# Sch_Raspi_Hat.net
KiCad netlist of a schematic drawn in Altium Designer
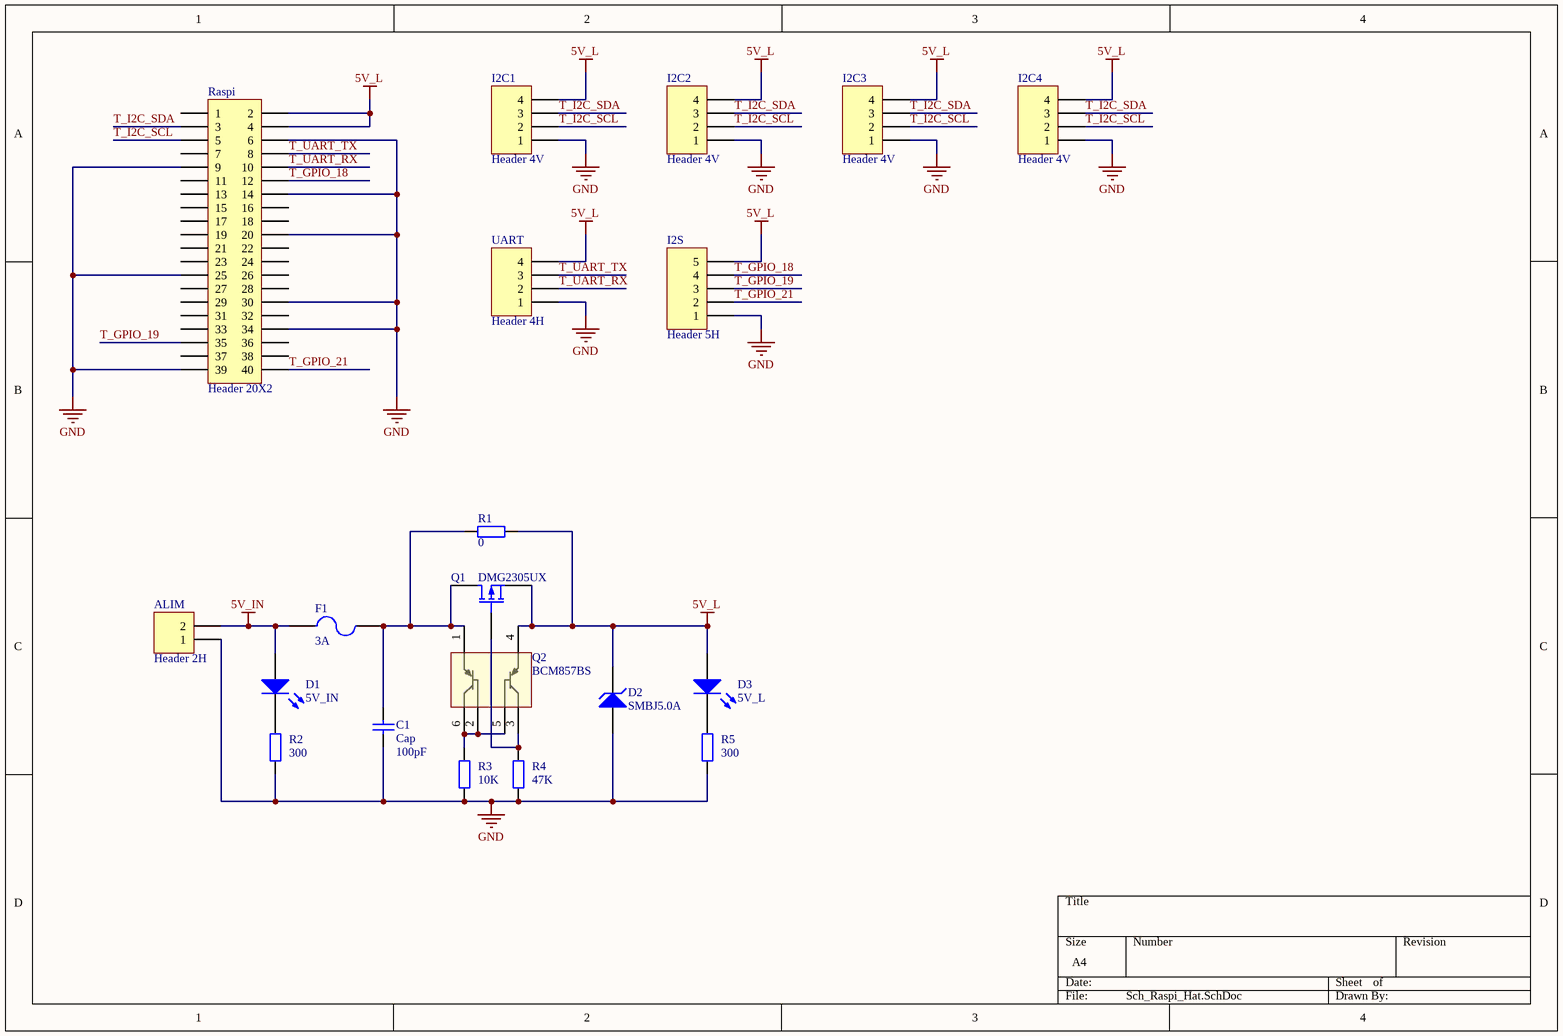
[diagram p0: Sch_Raspi_Hat.SchDoc]

(export (version "E")
  (design (tool "Eeschema 10.0.6"))
  (components
    (comp (ref "ALIM")
      (value "Header 2H")
      (footprint "Molex_MiniFitJr_2x1H")
      (description "Header, 2-Pin, Right Angle")
      (fields (field (name "PUBLISHER") "Altium Limited"))
      (libsource (lib "Miscellaneous Connectors") (part "Header 2H"))
    )
    (comp (ref "C1")
      (value "Cap")
      (footprint "Capacitor 1206")
      (description "Capacitor")
      (fields (field (name "ALTIUM_VALUE") "100pF") (field (name "PUBLISHER") "Altium Limited"))
      (libsource (lib "Miscellaneous Devices") (part "Cap"))
    )
    (comp (ref "D1")
      (value "5V_IN")
      (footprint "KP-3216SEC")
      (description "Typical RED, GREEN, YELLOW, AMBER GaAs LED")
      (fields (field (name "PUBLISHER") "Altium Limited"))
      (libsource (lib "Miscellaneous Devices") (part "LED2"))
    )
    (comp (ref "D2")
      (value "SMBJ5.0A")
      (footprint "SMB")
      (description "Zener Diode")
      (fields (field (name "PUBLISHER") "Altium Limited"))
      (libsource (lib "Miscellaneous Devices") (part "D Zener"))
    )
    (comp (ref "D3")
      (value "5V_L")
      (footprint "KP-3216SEC")
      (description "Typical RED, GREEN, YELLOW, AMBER GaAs LED")
      (fields (field (name "PUBLISHER") "Altium Limited"))
      (libsource (lib "Miscellaneous Devices") (part "LED2"))
    )
    (comp (ref "F1")
      (value "3A")
      (footprint "Resistor 1206")
      (description "Fuse")
      (fields (field (name "PUBLISHER") "Altium Limited"))
      (libsource (lib "Miscellaneous Devices") (part "Fuse 2"))
    )
    (comp (ref "I2C1")
      (value "Header 4V")
      (footprint "B4BXHALFSN")
      (description "Header, 4-Pin, Right Angle")
      (fields (field (name "PUBLISHER") "Altium Limited"))
      (libsource (lib "Miscellaneous Connectors") (part "Header 4H"))
    )
    (comp (ref "I2C2")
      (value "Header 4V")
      (footprint "B4BXHALFSN")
      (description "Header, 4-Pin, Right Angle")
      (fields (field (name "PUBLISHER") "Altium Limited"))
      (libsource (lib "Miscellaneous Connectors") (part "Header 4H"))
    )
    (comp (ref "I2C3")
      (value "Header 4V")
      (footprint "B4BXHALFSN")
      (description "Header, 4-Pin, Right Angle")
      (fields (field (name "PUBLISHER") "Altium Limited"))
      (libsource (lib "Miscellaneous Connectors") (part "Header 4H"))
    )
    (comp (ref "I2C4")
      (value "Header 4V")
      (footprint "B4BXHALFSN")
      (description "Header, 4-Pin, Right Angle")
      (fields (field (name "PUBLISHER") "Altium Limited"))
      (libsource (lib "Miscellaneous Connectors") (part "Header 4H"))
    )
    (comp (ref "I2S")
      (value "Header 5H")
      (footprint "S5B-XH-A")
      (description "Header, 5-Pin, Right Angle")
      (fields (field (name "PUBLISHER") "Altium Limited"))
      (libsource (lib "Miscellaneous Connectors") (part "Header 5H"))
    )
    (comp (ref "Q1")
      (value "DMG2305UX")
      (footprint "SOT23_L")
      (description "P-Channel MOSFET")
      (fields (field (name "PUBLISHER") "Altium Limited"))
      (libsource (lib "Miscellaneous Devices") (part "MOSFET-P"))
    )
    (comp (ref "Q2")
      (value "BCM857BS")
      (footprint "SOT65P210X110-6N")
      (description "Transistor")
      (libsource (lib "SamacSys") (part "BCM857BS"))
    )
    (comp (ref "R1")
      (value "0")
      (footprint "Resistor 1206")
      (description "Resistor")
      (fields (field (name "Comment") "Res2") (field (name "PUBLISHER") "Altium Limited"))
      (libsource (lib "") (part "Res2_1"))
    )
    (comp (ref "R2")
      (value "300")
      (footprint "Resistor 1206")
      (description "Resistor")
      (fields (field (name "Comment") "Res2") (field (name "PUBLISHER") "Altium Limited"))
      (libsource (lib "Miscellaneous Devices") (part "Res2"))
    )
    (comp (ref "R3")
      (value "10K")
      (footprint "Resistor 1206")
      (description "Resistor")
      (fields (field (name "Comment") "Res2") (field (name "PUBLISHER") "Altium Limited"))
      (libsource (lib "Miscellaneous Devices") (part "Res2"))
    )
    (comp (ref "R4")
      (value "47K")
      (footprint "Resistor 1206")
      (description "Resistor")
      (fields (field (name "Comment") "Res2") (field (name "PUBLISHER") "Altium Limited"))
      (libsource (lib "Miscellaneous Devices") (part "Res2"))
    )
    (comp (ref "R5")
      (value "300")
      (footprint "Resistor 1206")
      (description "Resistor")
      (fields (field (name "Comment") "Res2") (field (name "PUBLISHER") "Altium Limited"))
      (libsource (lib "Miscellaneous Devices") (part "Res2"))
    )
    (comp (ref "Raspi")
      (value "Header 20X2")
      (footprint "HDR2X20")
      (description "Header, 20-Pin, Dual row")
      (fields (field (name "PUBLISHER") "Altium Limited"))
      (libsource (lib "Miscellaneous Connectors") (part "Header 20X2"))
    )
    (comp (ref "UART")
      (value "Header 4H")
      (footprint "S4B-XH-A")
      (description "Header, 4-Pin, Right Angle")
      (fields (field (name "PUBLISHER") "Altium Limited"))
      (libsource (lib "Miscellaneous Connectors") (part "Header 4H"))
    )
  )
  (nets
    (net (code "1") (name "/T_GPIO_18") (class "Default")
      (node (ref "I2S") (pin "4") (pinfunction "4_4") (pintype "passive"))
      (node (ref "Raspi") (pin "12") (pinfunction "12_12") (pintype "passive"))
    )
    (net (code "2") (name "/T_GPIO_19") (class "Default")
      (node (ref "I2S") (pin "3") (pinfunction "3_3") (pintype "passive"))
      (node (ref "Raspi") (pin "35") (pinfunction "35_35") (pintype "passive"))
    )
    (net (code "3") (name "/T_GPIO_21") (class "Default")
      (node (ref "I2S") (pin "2") (pinfunction "2_2") (pintype "passive"))
      (node (ref "Raspi") (pin "40") (pinfunction "40_40") (pintype "passive"))
    )
    (net (code "4") (name "/T_I2C_SCL") (class "Default")
      (node (ref "I2C1") (pin "2") (pinfunction "2_2") (pintype "passive"))
      (node (ref "I2C2") (pin "2") (pinfunction "2_2") (pintype "passive"))
      (node (ref "I2C3") (pin "2") (pinfunction "2_2") (pintype "passive"))
      (node (ref "I2C4") (pin "2") (pinfunction "2_2") (pintype "passive"))
      (node (ref "Raspi") (pin "5") (pinfunction "5_5") (pintype "passive"))
    )
    (net (code "5") (name "/T_I2C_SDA") (class "Default")
      (node (ref "I2C1") (pin "3") (pinfunction "3_3") (pintype "passive"))
      (node (ref "I2C2") (pin "3") (pinfunction "3_3") (pintype "passive"))
      (node (ref "I2C3") (pin "3") (pinfunction "3_3") (pintype "passive"))
      (node (ref "I2C4") (pin "3") (pinfunction "3_3") (pintype "passive"))
      (node (ref "Raspi") (pin "3") (pinfunction "3_3") (pintype "passive"))
    )
    (net (code "6") (name "/T_UART_RX") (class "Default")
      (node (ref "Raspi") (pin "10") (pinfunction "10_10") (pintype "passive"))
      (node (ref "UART") (pin "2") (pinfunction "2_2") (pintype "passive"))
    )
    (net (code "7") (name "/T_UART_TX") (class "Default")
      (node (ref "Raspi") (pin "8") (pinfunction "8_8") (pintype "passive"))
      (node (ref "UART") (pin "3") (pinfunction "3_3") (pintype "passive"))
    )
    (net (code "8") (name "5V_IN") (class "Default")
      (node (ref "ALIM") (pin "2") (pinfunction "2_2") (pintype "passive"))
      (node (ref "D1") (pin "1") (pinfunction "A_1") (pintype "passive"))
      (node (ref "F1") (pin "1") (pinfunction "1_1") (pintype "passive"))
    )
    (net (code "9") (name "5V_L") (class "Default")
      (node (ref "D2") (pin "2") (pinfunction "K_2") (pintype "passive"))
      (node (ref "D3") (pin "1") (pinfunction "A_1") (pintype "passive"))
      (node (ref "I2C1") (pin "4") (pinfunction "4_4") (pintype "passive"))
      (node (ref "I2C2") (pin "4") (pinfunction "4_4") (pintype "passive"))
      (node (ref "I2C3") (pin "4") (pinfunction "4_4") (pintype "passive"))
      (node (ref "I2C4") (pin "4") (pinfunction "4_4") (pintype "passive"))
      (node (ref "I2S") (pin "5") (pinfunction "5_5") (pintype "passive"))
      (node (ref "Q1") (pin "3") (pinfunction "S_3") (pintype "passive"))
      (node (ref "Q2") (pin "4") (pinfunction "EMITTER_TR2_4") (pintype "passive"))
      (node (ref "R1") (pin "1") (pinfunction "1_1") (pintype "passive"))
      (node (ref "Raspi") (pin "2") (pinfunction "2_2") (pintype "passive"))
      (node (ref "Raspi") (pin "4") (pinfunction "4_4") (pintype "passive"))
      (node (ref "UART") (pin "4") (pinfunction "4_4") (pintype "passive"))
    )
    (net (code "10") (name "GND") (class "Default")
      (node (ref "ALIM") (pin "1") (pinfunction "1_1") (pintype "passive"))
      (node (ref "C1") (pin "1") (pinfunction "1_1") (pintype "passive"))
      (node (ref "D2") (pin "1") (pinfunction "A_1") (pintype "passive"))
      (node (ref "I2C1") (pin "1") (pinfunction "1_1") (pintype "passive"))
      (node (ref "I2C2") (pin "1") (pinfunction "1_1") (pintype "passive"))
      (node (ref "I2C3") (pin "1") (pinfunction "1_1") (pintype "passive"))
      (node (ref "I2C4") (pin "1") (pinfunction "1_1") (pintype "passive"))
      (node (ref "I2S") (pin "1") (pinfunction "1_1") (pintype "passive"))
      (node (ref "R2") (pin "1") (pinfunction "1_1") (pintype "passive"))
      (node (ref "R3") (pin "1") (pinfunction "1_1") (pintype "passive"))
      (node (ref "R4") (pin "1") (pinfunction "1_1") (pintype "passive"))
      (node (ref "R5") (pin "1") (pinfunction "1_1") (pintype "passive"))
      (node (ref "Raspi") (pin "14") (pinfunction "14_14") (pintype "passive"))
      (node (ref "Raspi") (pin "20") (pinfunction "20_20") (pintype "passive"))
      (node (ref "Raspi") (pin "25") (pinfunction "25_25") (pintype "passive"))
      (node (ref "Raspi") (pin "30") (pinfunction "30_30") (pintype "passive"))
      (node (ref "Raspi") (pin "34") (pinfunction "34_34") (pintype "passive"))
      (node (ref "Raspi") (pin "39") (pinfunction "39_39") (pintype "passive"))
      (node (ref "Raspi") (pin "6") (pinfunction "6_6") (pintype "passive"))
      (node (ref "Raspi") (pin "9") (pinfunction "9_9") (pintype "passive"))
      (node (ref "UART") (pin "1") (pinfunction "1_1") (pintype "passive"))
    )
    (net (code "11") (name "Net-(D1-K)") (class "Default")
      (node (ref "D1") (pin "2") (pinfunction "K_2") (pintype "passive"))
      (node (ref "R2") (pin "2") (pinfunction "2_2") (pintype "passive"))
    )
    (net (code "12") (name "Net-(D3-K)") (class "Default")
      (node (ref "D3") (pin "2") (pinfunction "K_2") (pintype "passive"))
      (node (ref "R5") (pin "2") (pinfunction "2_2") (pintype "passive"))
    )
    (net (code "13") (name "Net-(Q1-D)") (class "Default")
      (node (ref "C1") (pin "2") (pinfunction "2_2") (pintype "passive"))
      (node (ref "F1") (pin "2") (pinfunction "2_2") (pintype "passive"))
      (node (ref "Q1") (pin "1") (pinfunction "D_1") (pintype "passive"))
      (node (ref "Q2") (pin "1") (pinfunction "EMITTER_TR1_1") (pintype "passive"))
      (node (ref "R1") (pin "2") (pinfunction "2_2") (pintype "passive"))
    )
    (net (code "14") (name "Net-(Q1-G)") (class "Default")
      (node (ref "Q1") (pin "2") (pinfunction "G_2") (pintype "passive"))
      (node (ref "Q2") (pin "3") (pinfunction "COLLECTOR_TR2_3") (pintype "passive"))
      (node (ref "R4") (pin "2") (pinfunction "2_2") (pintype "passive"))
    )
    (net (code "15") (name "Net-(Q2-BASE_TR1)") (class "Default")
      (node (ref "Q2") (pin "2") (pinfunction "BASE_TR1_2") (pintype "passive"))
      (node (ref "Q2") (pin "5") (pinfunction "BASE_TR2_5") (pintype "passive"))
      (node (ref "Q2") (pin "6") (pinfunction "COLLECTOR_TR1_6") (pintype "passive"))
      (node (ref "R3") (pin "2") (pinfunction "2_2") (pintype "passive"))
    )
    (net (code "16") (name "unconnected-(Raspi-Pad1)") (class "Default")
      (node (ref "Raspi") (pin "1") (pinfunction "1_1") (pintype "passive"))
    )
    (net (code "17") (name "unconnected-(Raspi-Pad7)") (class "Default")
      (node (ref "Raspi") (pin "7") (pinfunction "7_7") (pintype "passive"))
    )
    (net (code "18") (name "unconnected-(Raspi-Pad11)") (class "Default")
      (node (ref "Raspi") (pin "11") (pinfunction "11_11") (pintype "passive"))
    )
    (net (code "19") (name "unconnected-(Raspi-Pad13)") (class "Default")
      (node (ref "Raspi") (pin "13") (pinfunction "13_13") (pintype "passive"))
    )
    (net (code "20") (name "unconnected-(Raspi-Pad15)") (class "Default")
      (node (ref "Raspi") (pin "15") (pinfunction "15_15") (pintype "passive"))
    )
    (net (code "21") (name "unconnected-(Raspi-Pad16)") (class "Default")
      (node (ref "Raspi") (pin "16") (pinfunction "16_16") (pintype "passive"))
    )
    (net (code "22") (name "unconnected-(Raspi-Pad17)") (class "Default")
      (node (ref "Raspi") (pin "17") (pinfunction "17_17") (pintype "passive"))
    )
    (net (code "23") (name "unconnected-(Raspi-Pad18)") (class "Default")
      (node (ref "Raspi") (pin "18") (pinfunction "18_18") (pintype "passive"))
    )
    (net (code "24") (name "unconnected-(Raspi-Pad19)") (class "Default")
      (node (ref "Raspi") (pin "19") (pinfunction "19_19") (pintype "passive"))
    )
    (net (code "25") (name "unconnected-(Raspi-Pad21)") (class "Default")
      (node (ref "Raspi") (pin "21") (pinfunction "21_21") (pintype "passive"))
    )
    (net (code "26") (name "unconnected-(Raspi-Pad22)") (class "Default")
      (node (ref "Raspi") (pin "22") (pinfunction "22_22") (pintype "passive"))
    )
    (net (code "27") (name "unconnected-(Raspi-Pad23)") (class "Default")
      (node (ref "Raspi") (pin "23") (pinfunction "23_23") (pintype "passive"))
    )
    (net (code "28") (name "unconnected-(Raspi-Pad24)") (class "Default")
      (node (ref "Raspi") (pin "24") (pinfunction "24_24") (pintype "passive"))
    )
    (net (code "29") (name "unconnected-(Raspi-Pad26)") (class "Default")
      (node (ref "Raspi") (pin "26") (pinfunction "26_26") (pintype "passive"))
    )
    (net (code "30") (name "unconnected-(Raspi-Pad27)") (class "Default")
      (node (ref "Raspi") (pin "27") (pinfunction "27_27") (pintype "passive"))
    )
    (net (code "31") (name "unconnected-(Raspi-Pad28)") (class "Default")
      (node (ref "Raspi") (pin "28") (pinfunction "28_28") (pintype "passive"))
    )
    (net (code "32") (name "unconnected-(Raspi-Pad29)") (class "Default")
      (node (ref "Raspi") (pin "29") (pinfunction "29_29") (pintype "passive"))
    )
    (net (code "33") (name "unconnected-(Raspi-Pad31)") (class "Default")
      (node (ref "Raspi") (pin "31") (pinfunction "31_31") (pintype "passive"))
    )
    (net (code "34") (name "unconnected-(Raspi-Pad32)") (class "Default")
      (node (ref "Raspi") (pin "32") (pinfunction "32_32") (pintype "passive"))
    )
    (net (code "35") (name "unconnected-(Raspi-Pad33)") (class "Default")
      (node (ref "Raspi") (pin "33") (pinfunction "33_33") (pintype "passive"))
    )
    (net (code "36") (name "unconnected-(Raspi-Pad36)") (class "Default")
      (node (ref "Raspi") (pin "36") (pinfunction "36_36") (pintype "passive"))
    )
    (net (code "37") (name "unconnected-(Raspi-Pad37)") (class "Default")
      (node (ref "Raspi") (pin "37") (pinfunction "37_37") (pintype "passive"))
    )
    (net (code "38") (name "unconnected-(Raspi-Pad38)") (class "Default")
      (node (ref "Raspi") (pin "38") (pinfunction "38_38") (pintype "passive"))
    )
  )
)
